# RocketWatch-TOP.net
KiCad netlist of a schematic drawn in EAGLE
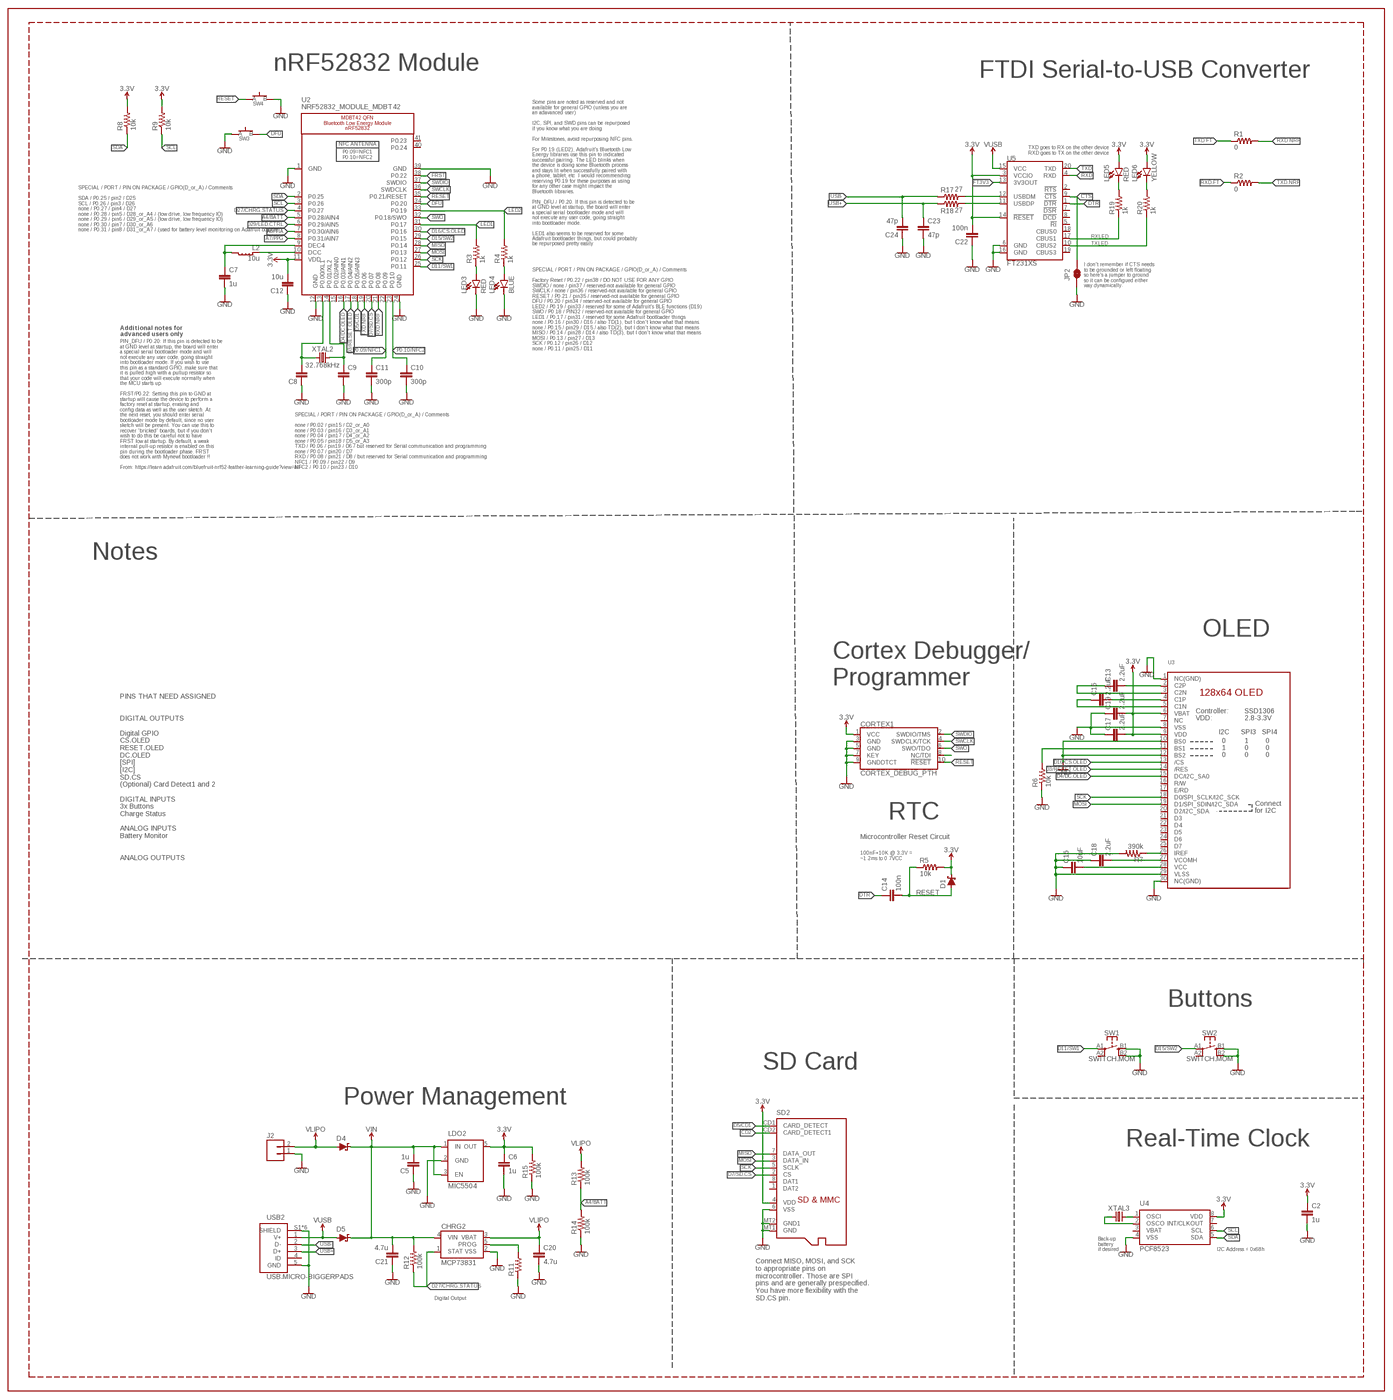
[diagram p0: schematic, sheet 1, overview]
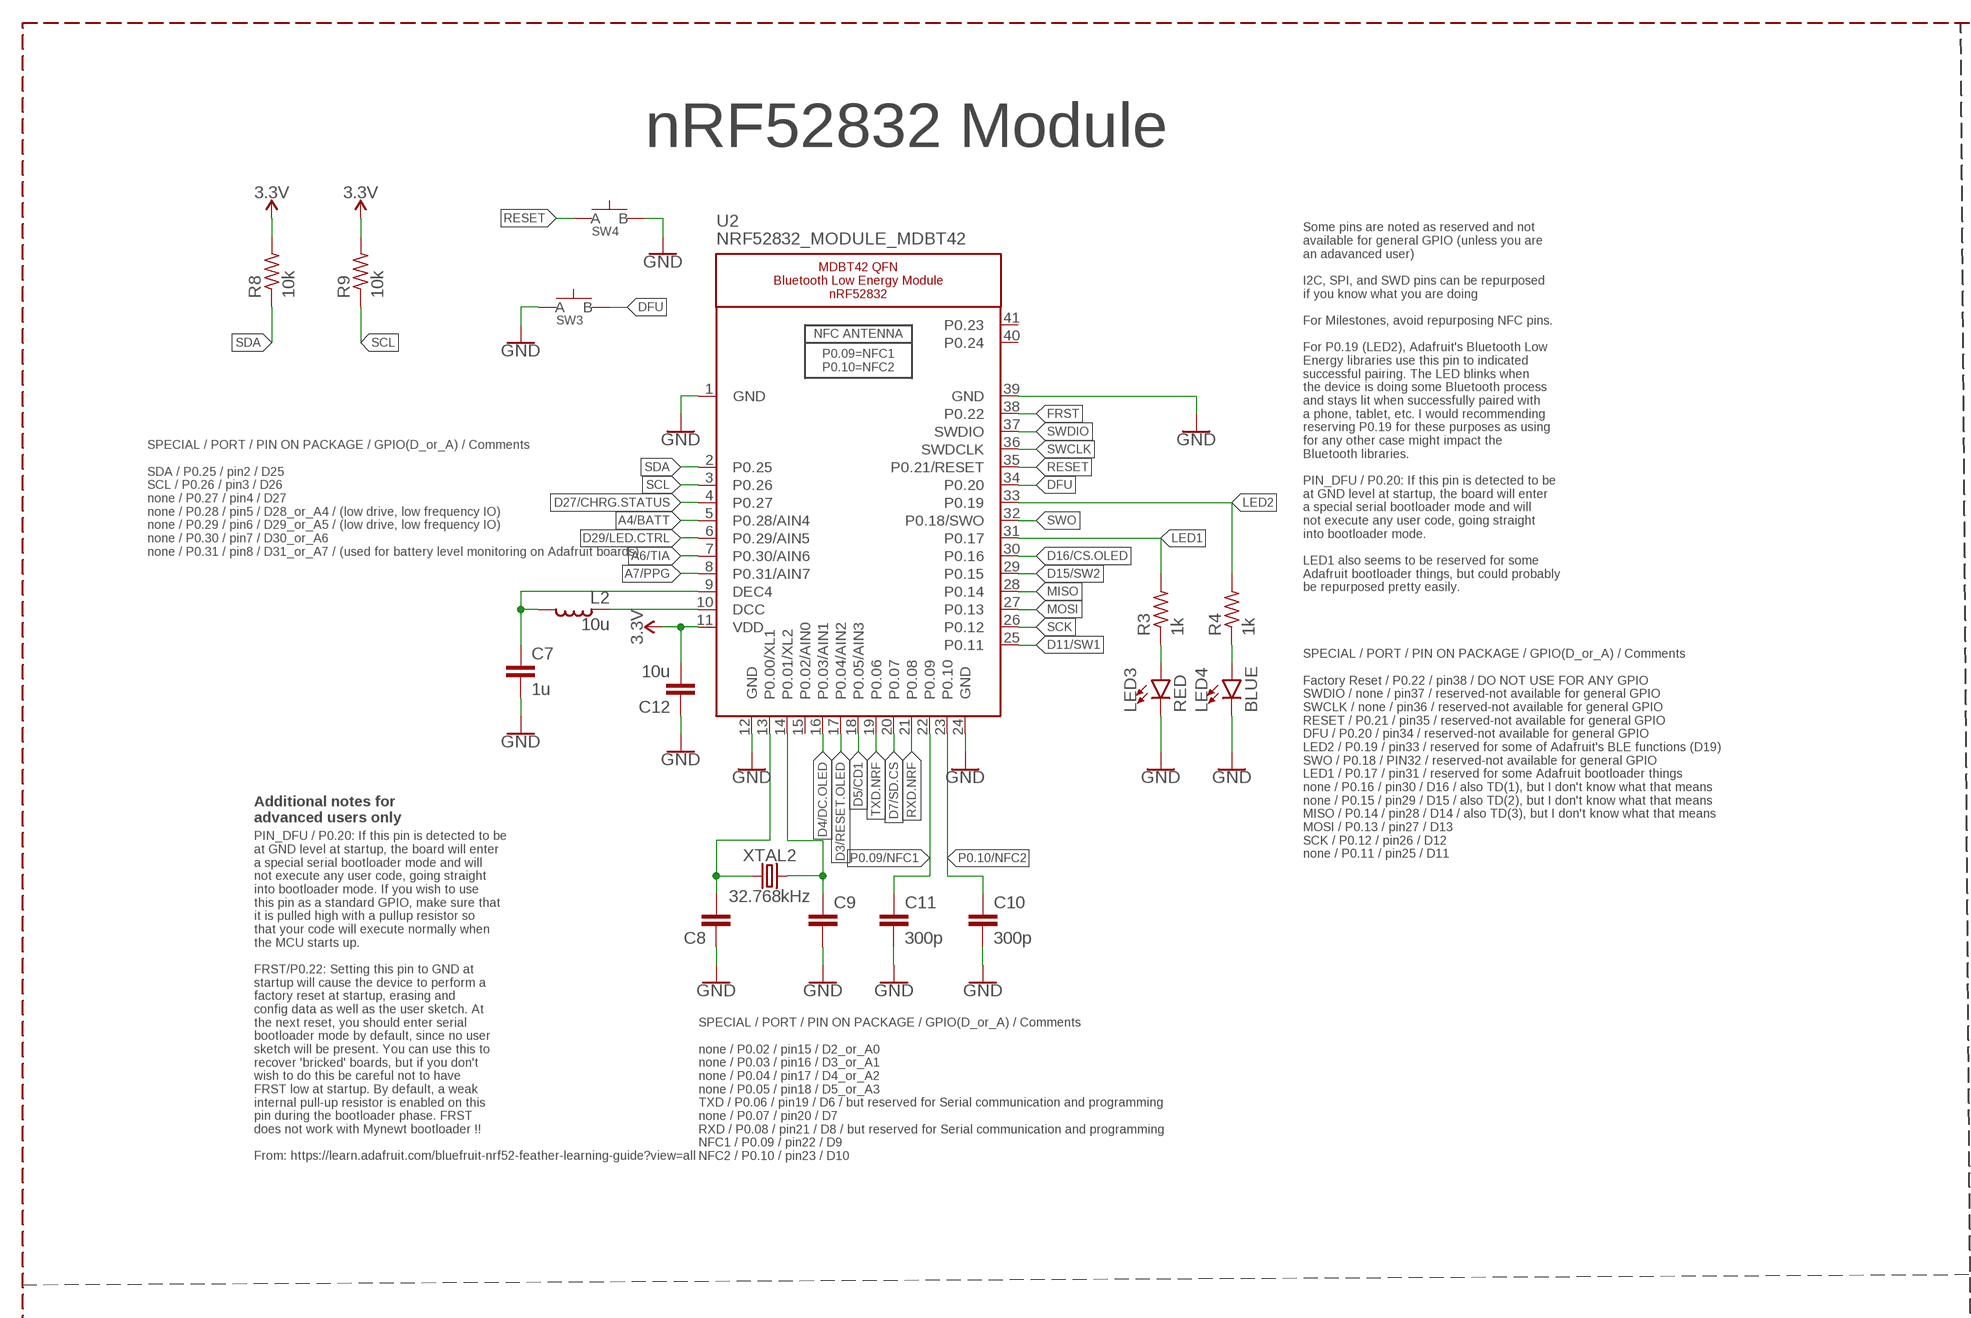
[diagram p1: schematic, sheet 1, part 1 of 4]
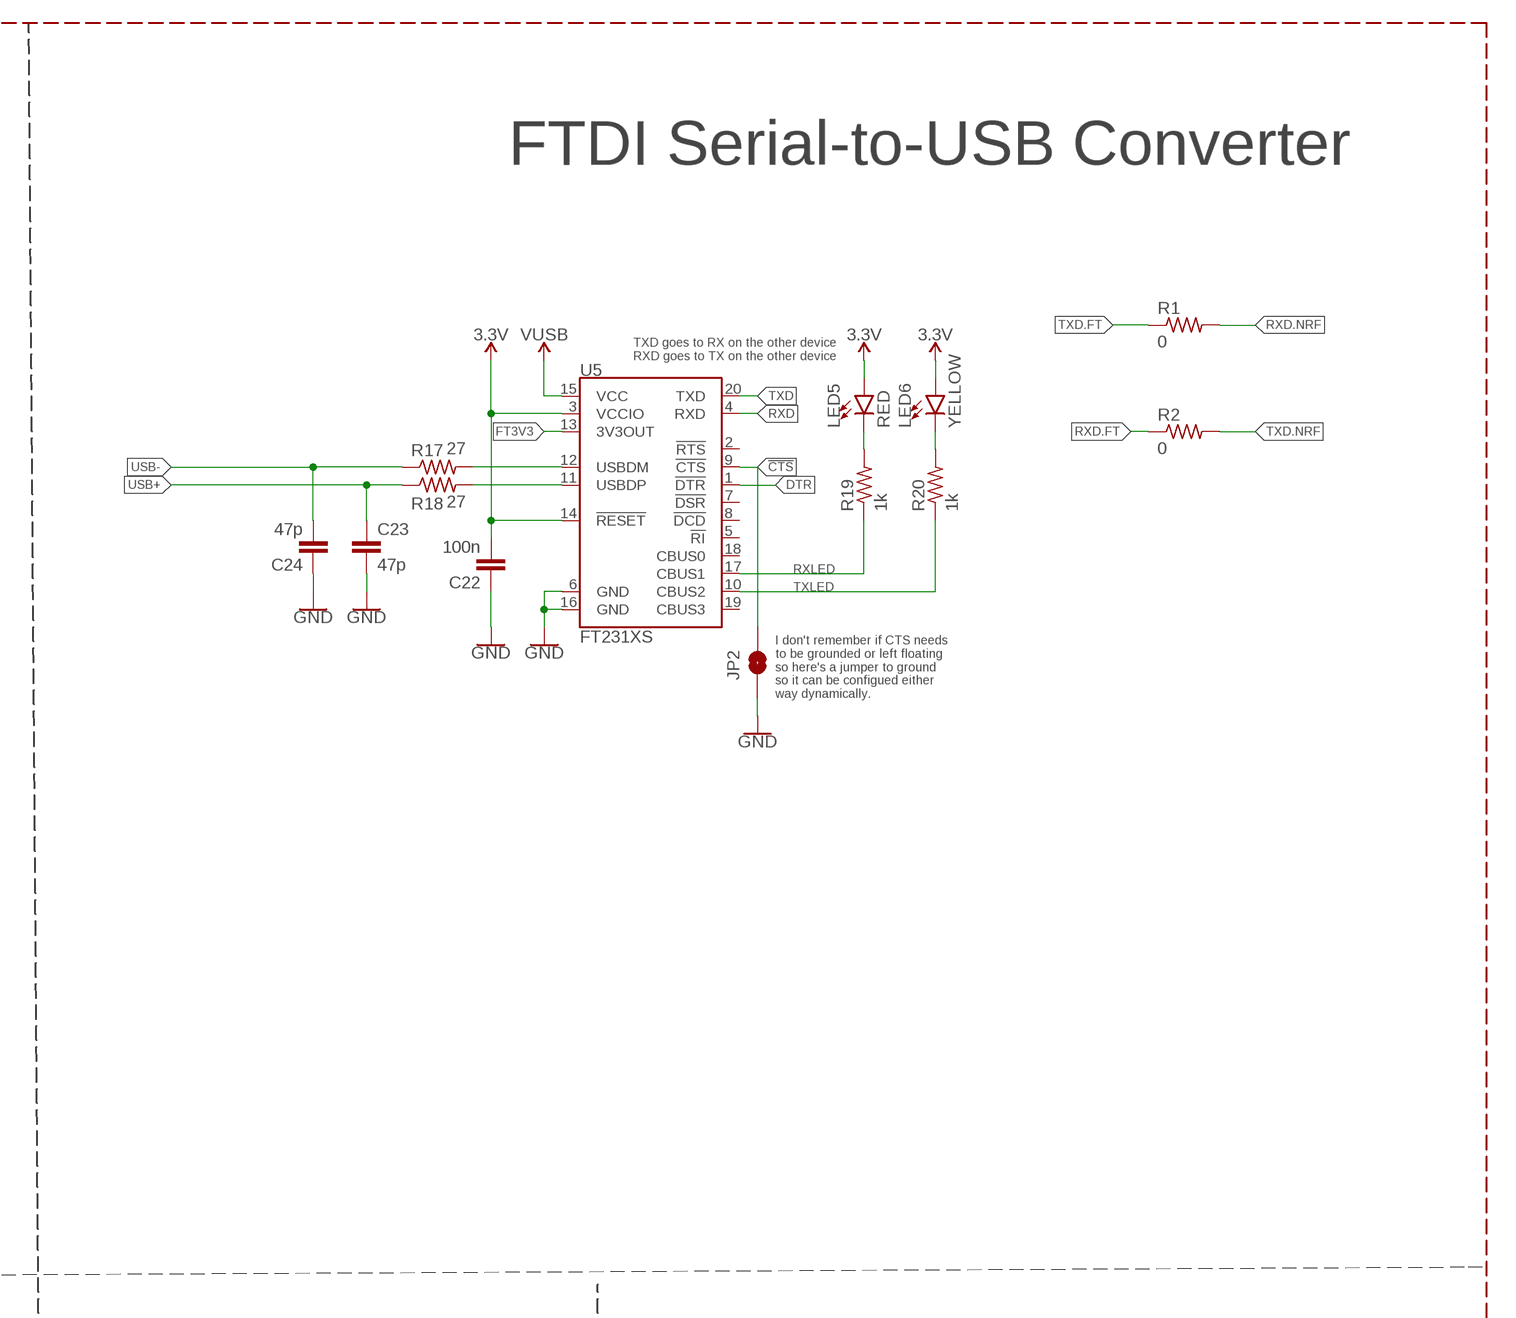
[diagram p2: schematic, sheet 1, part 2 of 4]
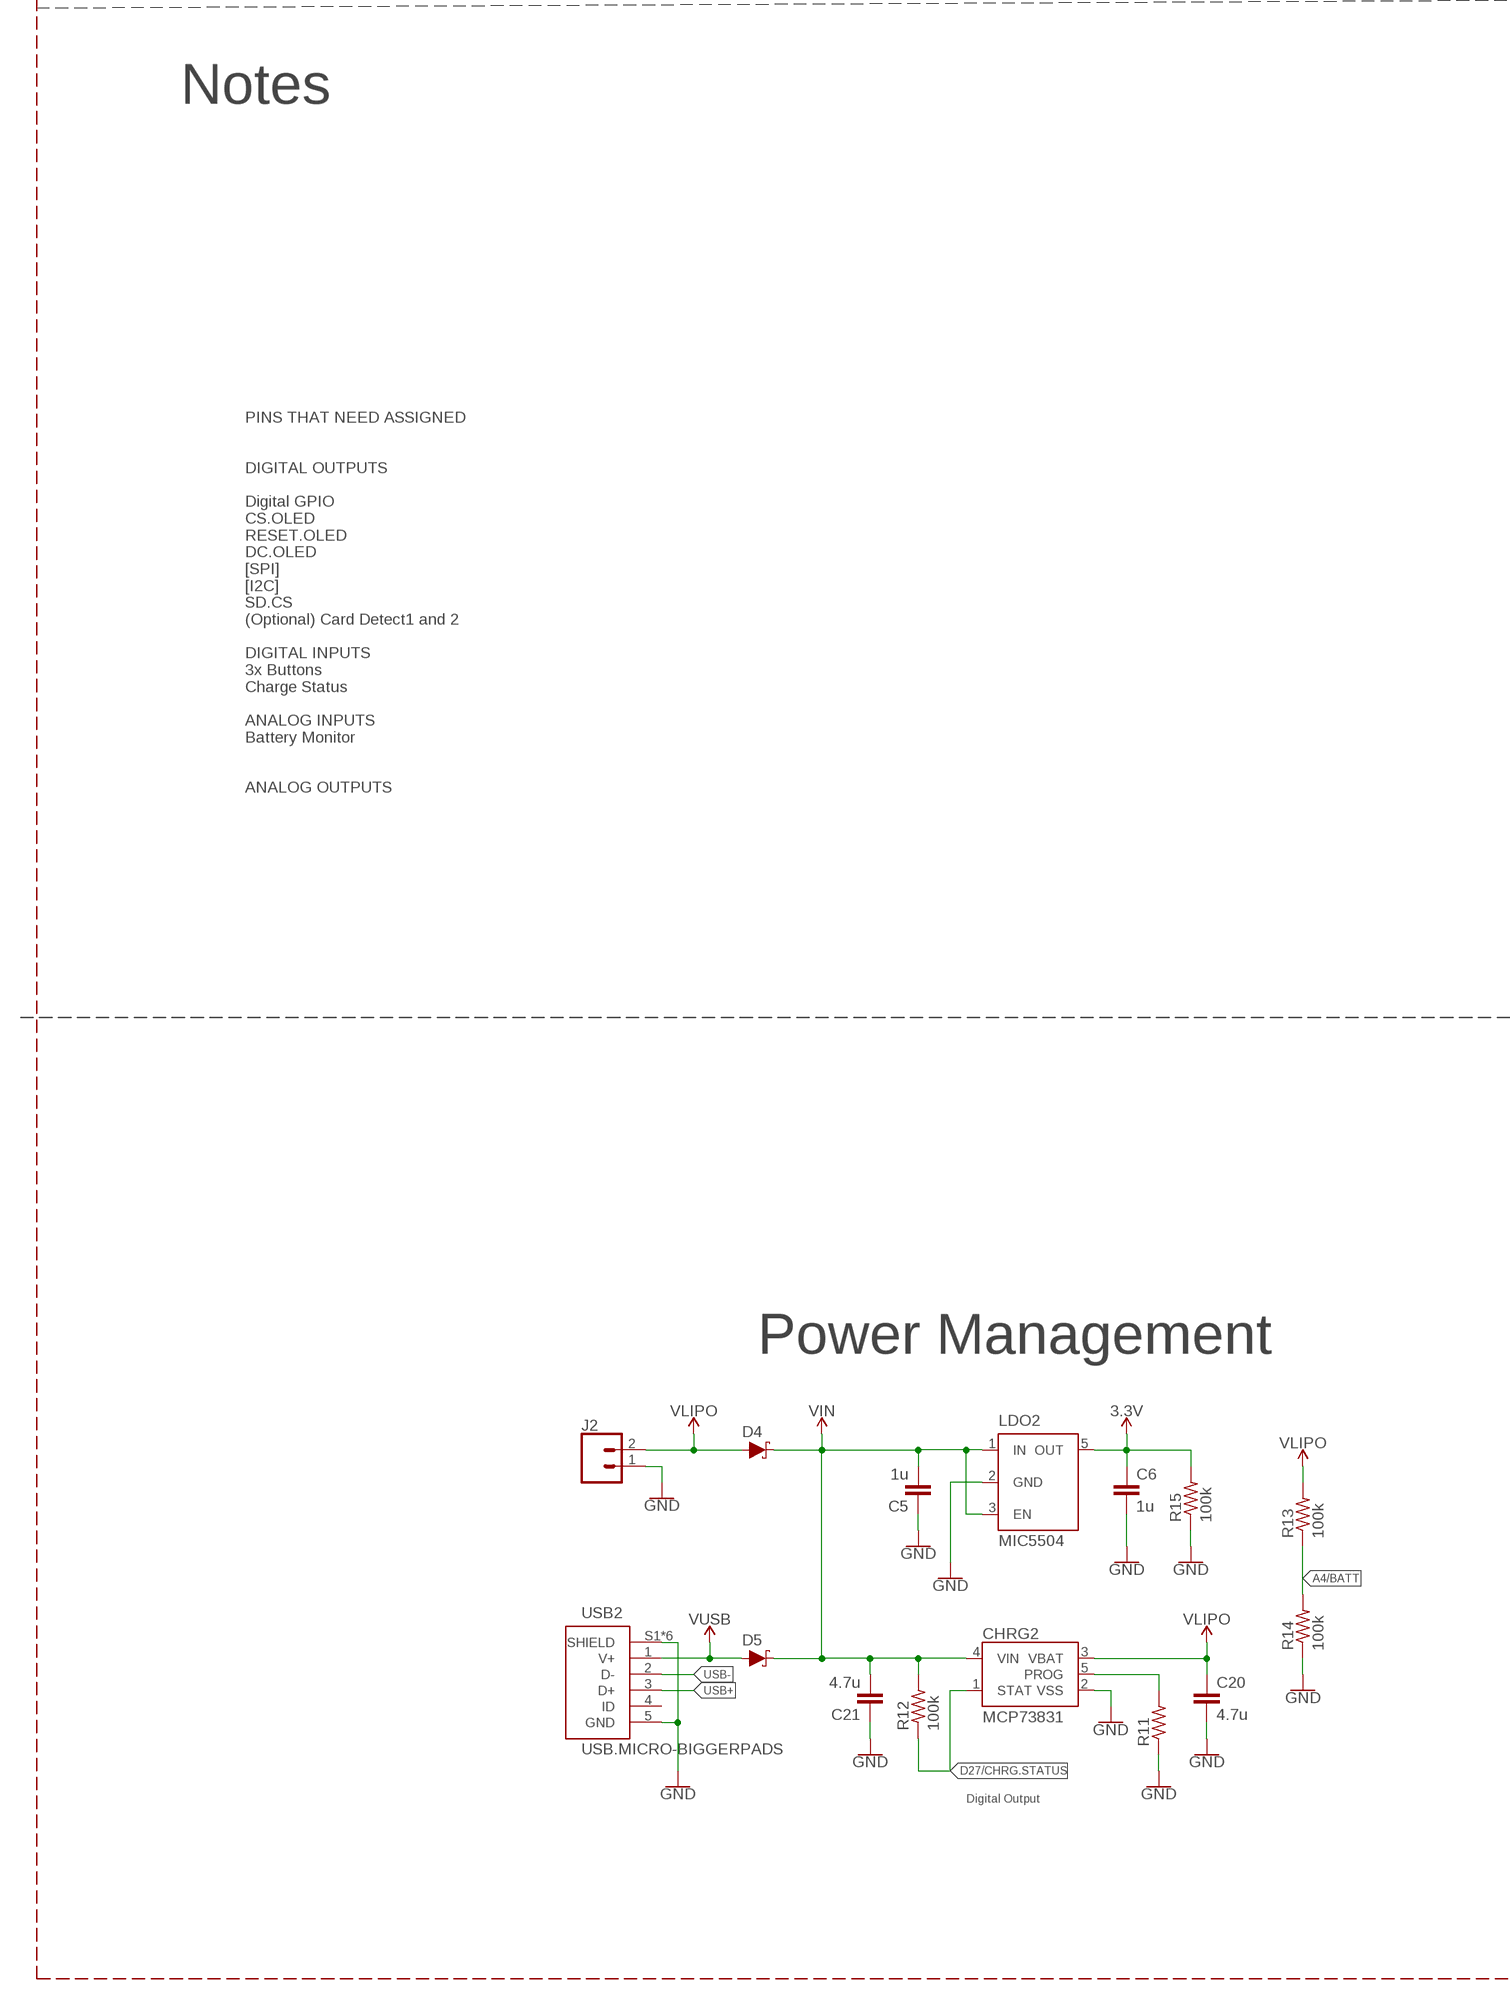
[diagram p3: schematic, sheet 1, part 3 of 4]
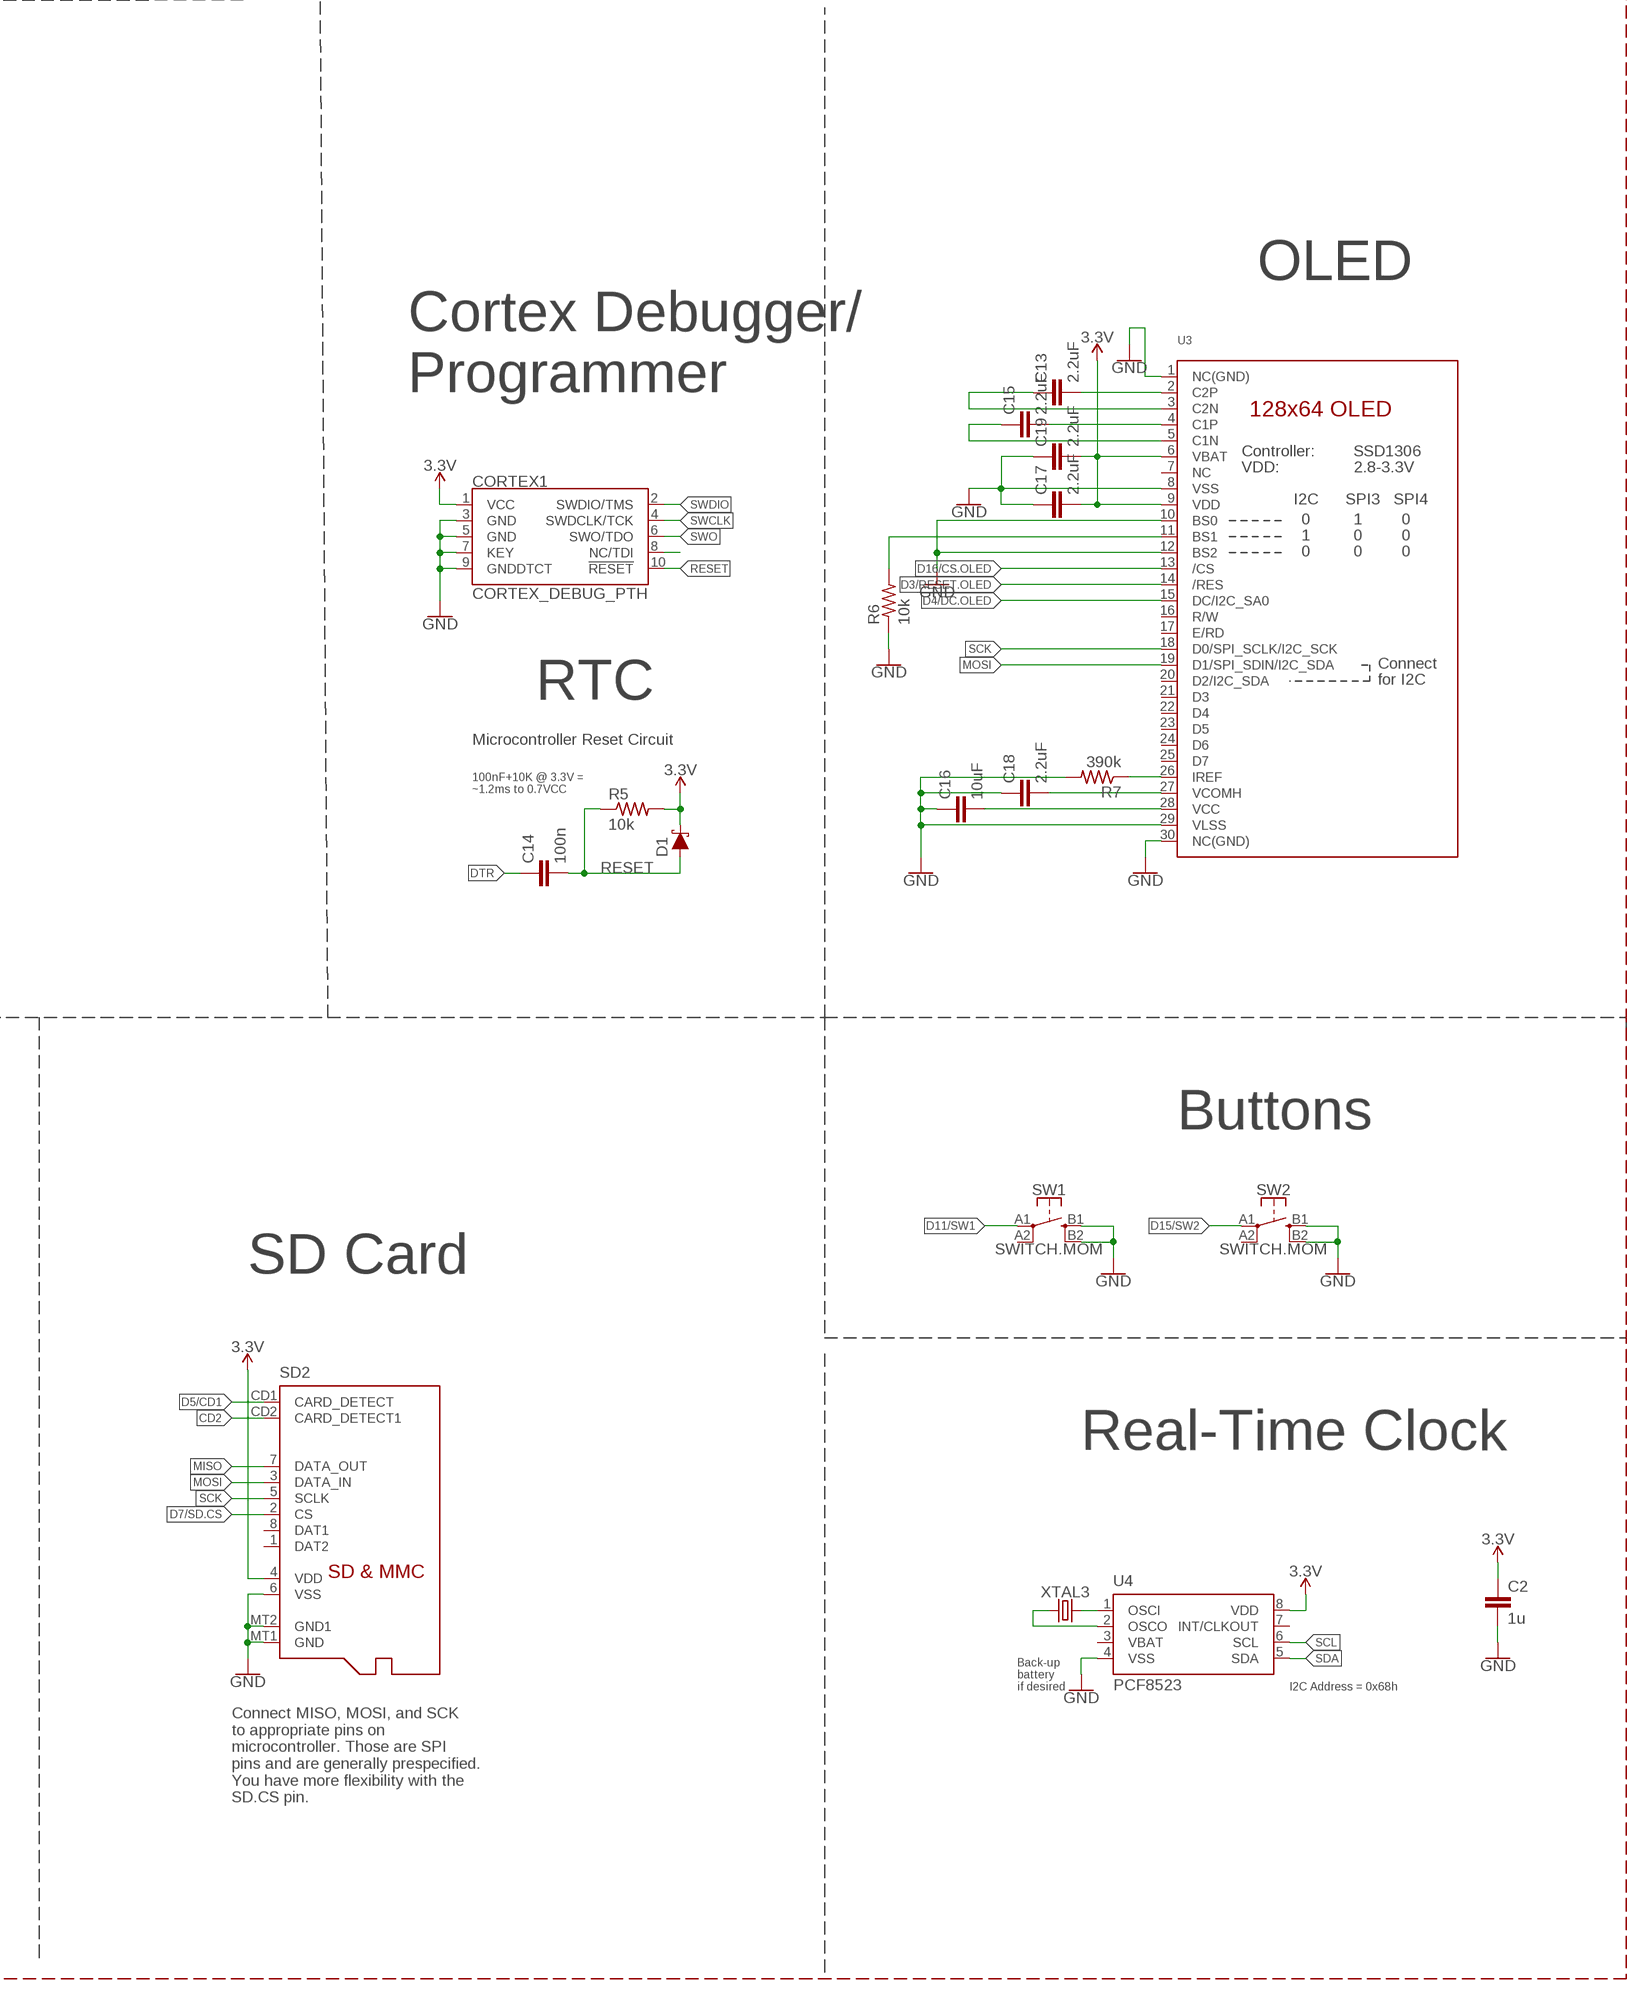
[diagram p4: schematic, sheet 1, part 4 of 4]

(export (version "E")
  (design (tool "Eeschema 10.0.6"))
  (components
    (comp (ref "C2")
      (value "1u")
      (footprint "eagle-import:C0603")
      (libsource (lib "eagle-import") (part "CAPACITOR0603"))
    )
    (comp (ref "C5")
      (value "1u")
      (footprint "eagle-import:C0603")
      (libsource (lib "eagle-import") (part "CAPACITOR0603"))
    )
    (comp (ref "C6")
      (value "1u")
      (footprint "eagle-import:C0603")
      (libsource (lib "eagle-import") (part "CAPACITOR0603"))
    )
    (comp (ref "C7")
      (value "1u")
      (footprint "eagle-import:C0603")
      (libsource (lib "eagle-import") (part "CAPACITOR0603"))
    )
    (comp (ref "C8")
      (value "CAPACITOR0603")
      (footprint "eagle-import:C0603")
      (libsource (lib "eagle-import") (part "CAPACITOR0603"))
    )
    (comp (ref "C9")
      (value "CAPACITOR0603")
      (footprint "eagle-import:C0603")
      (libsource (lib "eagle-import") (part "CAPACITOR0603"))
    )
    (comp (ref "C10")
      (value "300p")
      (footprint "eagle-import:C0603")
      (libsource (lib "eagle-import") (part "CAPACITOR0603"))
    )
    (comp (ref "C11")
      (value "300p")
      (footprint "eagle-import:C0603")
      (libsource (lib "eagle-import") (part "CAPACITOR0603"))
    )
    (comp (ref "C12")
      (value "10u")
      (footprint "eagle-import:C0805")
      (libsource (lib "eagle-import") (part "CAPACITOR0805"))
    )
    (comp (ref "C13")
      (value "2.2uF")
      (footprint "eagle-import:C0402")
      (libsource (lib "eagle-import") (part "CAPACITOR0402"))
    )
    (comp (ref "C14")
      (value "100n")
      (footprint "eagle-import:C0603")
      (libsource (lib "eagle-import") (part "CAPACITOR0603"))
    )
    (comp (ref "C15")
      (value "2.2uF")
      (footprint "eagle-import:C0402")
      (libsource (lib "eagle-import") (part "CAPACITOR0402"))
    )
    (comp (ref "C16")
      (value "10uF")
      (footprint "eagle-import:C0603")
      (libsource (lib "eagle-import") (part "CAPACITOR0603"))
    )
    (comp (ref "C17")
      (value "2.2uF")
      (footprint "eagle-import:C0402")
      (libsource (lib "eagle-import") (part "CAPACITOR0402"))
    )
    (comp (ref "C18")
      (value "2.2uF")
      (footprint "eagle-import:C0402")
      (libsource (lib "eagle-import") (part "CAPACITOR0402"))
    )
    (comp (ref "C19")
      (value "2.2uF")
      (footprint "eagle-import:C0402")
      (libsource (lib "eagle-import") (part "CAPACITOR0402"))
    )
    (comp (ref "C20")
      (value "4.7u")
      (footprint "eagle-import:C0603")
      (libsource (lib "eagle-import") (part "CAPACITOR0603"))
    )
    (comp (ref "C21")
      (value "4.7u")
      (footprint "eagle-import:C0603")
      (libsource (lib "eagle-import") (part "CAPACITOR0603"))
    )
    (comp (ref "C22")
      (value "100n")
      (footprint "eagle-import:C0603")
      (libsource (lib "eagle-import") (part "CAPACITOR0603"))
    )
    (comp (ref "C23")
      (value "47p")
      (footprint "eagle-import:C0603")
      (libsource (lib "eagle-import") (part "CAPACITOR0603"))
    )
    (comp (ref "C24")
      (value "47p")
      (footprint "eagle-import:C0603")
      (libsource (lib "eagle-import") (part "CAPACITOR0603"))
    )
    (comp (ref "CHRG2")
      (value "MCP73831")
      (footprint "eagle-import:SOT23-5")
      (libsource (lib "eagle-import") (part "MCP73831"))
    )
    (comp (ref "CORTEX1")
      (value "CORTEX_DEBUG_PTH")
      (footprint "eagle-import:2X5-PTH-1.27MM")
      (libsource (lib "eagle-import") (part "CORTEX_DEBUG_PTH"))
    )
    (comp (ref "D1")
      (value "SCHOTTKY-USC")
      (footprint "eagle-import:USC")
      (libsource (lib "eagle-import") (part "SCHOTTKY-USC"))
    )
    (comp (ref "D4")
      (value "SCHOTTKY-USC")
      (footprint "eagle-import:USC")
      (libsource (lib "eagle-import") (part "SCHOTTKY-USC"))
    )
    (comp (ref "D5")
      (value "SCHOTTKY-USC")
      (footprint "eagle-import:USC")
      (libsource (lib "eagle-import") (part "SCHOTTKY-USC"))
    )
    (comp (ref "J2")
      (value "CONN_02")
      (footprint "eagle-import:1X02")
      (libsource (lib "eagle-import") (part "CONN_02"))
    )
    (comp (ref "JP2")
      (value "JUMPER-SMT_2_NO_SILK")
      (footprint "eagle-import:SMT-JUMPER_2_NO_SILK")
      (libsource (lib "eagle-import") (part "JUMPER-SMT_2_NO_SILK"))
    )
    (comp (ref "L2")
      (value "10u")
      (footprint "eagle-import:L0603")
      (libsource (lib "eagle-import") (part "INDUCTOR0603"))
    )
    (comp (ref "LDO2")
      (value "MIC5504")
      (footprint "eagle-import:SOT23-5")
      (libsource (lib "eagle-import") (part "MIC5504"))
    )
    (comp (ref "LED3")
      (value "RED")
      (footprint "eagle-import:LED-0603")
      (libsource (lib "eagle-import") (part "LED0603"))
    )
    (comp (ref "LED4")
      (value "BLUE")
      (footprint "eagle-import:LED-0603")
      (libsource (lib "eagle-import") (part "LED0603"))
    )
    (comp (ref "LED5")
      (value "RED")
      (footprint "eagle-import:LED-0603")
      (libsource (lib "eagle-import") (part "LED0603"))
    )
    (comp (ref "LED6")
      (value "YELLOW")
      (footprint "eagle-import:LED-0603")
      (libsource (lib "eagle-import") (part "LED0603"))
    )
    (comp (ref "R1")
      (value "0")
      (footprint "eagle-import:R0603")
      (libsource (lib "eagle-import") (part "RESISTOR0603"))
    )
    (comp (ref "R2")
      (value "0")
      (footprint "eagle-import:R0603")
      (libsource (lib "eagle-import") (part "RESISTOR0603"))
    )
    (comp (ref "R3")
      (value "1k")
      (footprint "eagle-import:R0603")
      (libsource (lib "eagle-import") (part "RESISTOR0603"))
    )
    (comp (ref "R4")
      (value "1k")
      (footprint "eagle-import:R0603")
      (libsource (lib "eagle-import") (part "RESISTOR0603"))
    )
    (comp (ref "R5")
      (value "10k")
      (footprint "eagle-import:R0603")
      (libsource (lib "eagle-import") (part "RESISTOR0603"))
    )
    (comp (ref "R6")
      (value "10k")
      (footprint "eagle-import:R0603")
      (libsource (lib "eagle-import") (part "RESISTOR0603"))
    )
    (comp (ref "R7")
      (value "390k")
      (footprint "eagle-import:R0603")
      (libsource (lib "eagle-import") (part "RESISTOR0603"))
    )
    (comp (ref "R8")
      (value "10k")
      (footprint "eagle-import:R0603")
      (libsource (lib "eagle-import") (part "RESISTOR0603"))
    )
    (comp (ref "R9")
      (value "10k")
      (footprint "eagle-import:R0603")
      (libsource (lib "eagle-import") (part "RESISTOR0603"))
    )
    (comp (ref "R11")
      (value "RESISTOR0603")
      (footprint "eagle-import:R0603")
      (libsource (lib "eagle-import") (part "RESISTOR0603"))
    )
    (comp (ref "R12")
      (value "100k")
      (footprint "eagle-import:R0603")
      (libsource (lib "eagle-import") (part "RESISTOR0603"))
    )
    (comp (ref "R13")
      (value "100k")
      (footprint "eagle-import:R0603")
      (libsource (lib "eagle-import") (part "RESISTOR0603"))
    )
    (comp (ref "R14")
      (value "100k")
      (footprint "eagle-import:R0603")
      (libsource (lib "eagle-import") (part "RESISTOR0603"))
    )
    (comp (ref "R15")
      (value "100k")
      (footprint "eagle-import:R0603")
      (libsource (lib "eagle-import") (part "RESISTOR0603"))
    )
    (comp (ref "R17")
      (value "27")
      (footprint "eagle-import:R0603")
      (libsource (lib "eagle-import") (part "RESISTOR0603"))
    )
    (comp (ref "R18")
      (value "27")
      (footprint "eagle-import:R0603")
      (libsource (lib "eagle-import") (part "RESISTOR0603"))
    )
    (comp (ref "R19")
      (value "1k")
      (footprint "eagle-import:R0603")
      (libsource (lib "eagle-import") (part "RESISTOR0603"))
    )
    (comp (ref "R20")
      (value "1k")
      (footprint "eagle-import:R0603")
      (libsource (lib "eagle-import") (part "RESISTOR0603"))
    )
    (comp (ref "SD2")
      (value "MICROSD")
      (footprint "eagle-import:MICROSD")
      (libsource (lib "eagle-import") (part "MICROSD"))
    )
    (comp (ref "SW1")
      (value "SWITCH.MOM")
      (footprint "eagle-import:TACTILE_SWITCH_SMD_6.2MM_TALL")
      (libsource (lib "eagle-import") (part "SWITCH.MOM"))
    )
    (comp (ref "SW2")
      (value "SWITCH.MOM")
      (footprint "eagle-import:TACTILE_SWITCH_SMD_6.2MM_TALL")
      (libsource (lib "eagle-import") (part "SWITCH.MOM"))
    )
    (comp (ref "SW3")
      (value "SPST-PTS830GG140-COPY.1-3")
      (footprint "eagle-import:BUTTON-GULLWING")
      (libsource (lib "eagle-import") (part "SPST-PTS830GG140-COPY.1-3"))
    )
    (comp (ref "SW4")
      (value "SPST-PTS830GG140-COPY.1-3")
      (footprint "eagle-import:BUTTON-GULLWING")
      (libsource (lib "eagle-import") (part "SPST-PTS830GG140-COPY.1-3"))
    )
    (comp (ref "U2")
      (value "NRF52832_MODULE_MDBT42")
      (footprint "eagle-import:BLE_MODULE_RAYTAC_MDBT42")
      (libsource (lib "eagle-import") (part "NRF52832_MODULE_MDBT42"))
    )
    (comp (ref "U3")
      (value "DISP_OLED_UG-2864HSWEG01-NO-WRAPAROUND")
      (footprint "eagle-import:UG-2864HSWEG01_0.96IN_NO-WRAPAROUND")
      (libsource (lib "eagle-import") (part "DISP_OLED_UG-2864HSWEG01-NO-WRAPAROUND"))
    )
    (comp (ref "U4")
      (value "PCF8523")
      (footprint "eagle-import:SO8")
      (libsource (lib "eagle-import") (part "PCF8523"))
    )
    (comp (ref "U5")
      (value "FT231XS")
      (footprint "eagle-import:SSOP20_L")
      (libsource (lib "eagle-import") (part "FT231XS"))
    )
    (comp (ref "USB2")
      (value "USB.MICRO-BIGGERPADS")
      (footprint "eagle-import:USB-MICRO-01.BIGGERPADS")
      (libsource (lib "eagle-import") (part "USB.MICRO-BIGGERPADS"))
    )
    (comp (ref "XTAL2")
      (value "32.768kHz")
      (footprint "eagle-import:2-SMD.NOLEAD.2.0MMTO1.2MM")
      (libsource (lib "eagle-import") (part "CRYSTALECS-.327-12.5-12-C-TR"))
    )
    (comp (ref "XTAL3")
      (value "32.7680kHz")
      (footprint "eagle-import:2-SMD.NOLEAD.2.0MMTO1.2MM")
      (fields (field (name "FREQ") "32.7680KHZ"))
      (libsource (lib "eagle-import") (part "CRYSTALECS-.327-12.5-12-C-TR"))
    )
  )
  (nets
    (net (code "1") (name "/RXLED") (class "Default")
      (node (ref "R19") (pin "1") (pinfunction "1_1") (pintype "passive"))
      (node (ref "U5") (pin "17") (pinfunction "CBUS1_17") (pintype "bidirectional"))
    )
    (net (code "2") (name "/TXLED") (class "Default")
      (node (ref "R20") (pin "1") (pinfunction "1_1") (pintype "passive"))
      (node (ref "U5") (pin "10") (pinfunction "CBUS2_10") (pintype "bidirectional"))
    )
    (net (code "3") (name "/VBAT") (class "Default")
      (node (ref "U4") (pin "3") (pinfunction "VBAT_3") (pintype "power_in"))
    )
    (net (code "4") (name "/~{CTS}") (class "Default")
      (node (ref "JP2") (pin "2") (pinfunction "2_2") (pintype "passive"))
      (node (ref "U5") (pin "9") (pinfunction "~{CTS}_9") (pintype "bidirectional"))
    )
    (net (code "5") (name "3.3V") (class "Default")
      (node (ref "C12") (pin "2") (pinfunction "2_2") (pintype "passive"))
      (node (ref "C17") (pin "2") (pinfunction "2_2") (pintype "passive"))
      (node (ref "C19") (pin "2") (pinfunction "2_2") (pintype "passive"))
      (node (ref "C2") (pin "1") (pinfunction "1_1") (pintype "passive"))
      (node (ref "C22") (pin "2") (pinfunction "2_2") (pintype "passive"))
      (node (ref "C6") (pin "1") (pinfunction "1_1") (pintype "passive"))
      (node (ref "CORTEX1") (pin "1") (pinfunction "VCC_1") (pintype "bidirectional"))
      (node (ref "D1") (pin "-") (pinfunction "C_-") (pintype "passive"))
      (node (ref "LDO2") (pin "5") (pinfunction "OUT_5") (pintype "bidirectional"))
      (node (ref "LED5") (pin "A") (pinfunction "A_A") (pintype "passive"))
      (node (ref "LED6") (pin "A") (pinfunction "A_A") (pintype "passive"))
      (node (ref "R15") (pin "2") (pinfunction "2_2") (pintype "passive"))
      (node (ref "R5") (pin "2") (pinfunction "2_2") (pintype "passive"))
      (node (ref "R8") (pin "2") (pinfunction "2_2") (pintype "passive"))
      (node (ref "R9") (pin "2") (pinfunction "2_2") (pintype "passive"))
      (node (ref "SD2") (pin "4") (pinfunction "VDD_4") (pintype "power_in"))
      (node (ref "U2") (pin "11") (pinfunction "VDD_11") (pintype "bidirectional"))
      (node (ref "U3") (pin "6") (pinfunction "VBAT_6") (pintype "input"))
      (node (ref "U3") (pin "9") (pinfunction "VDD_9") (pintype "power_in"))
      (node (ref "U4") (pin "8") (pinfunction "VDD_8") (pintype "power_in"))
      (node (ref "U5") (pin "14") (pinfunction "~{RESET}_14") (pintype "bidirectional"))
      (node (ref "U5") (pin "3") (pinfunction "VCCIO_3") (pintype "bidirectional"))
    )
    (net (code "6") (name "A4{slash}BATT") (class "Default")
      (node (ref "R13") (pin "1") (pinfunction "1_1") (pintype "passive"))
      (node (ref "R14") (pin "2") (pinfunction "2_2") (pintype "passive"))
      (node (ref "U2") (pin "5") (pinfunction "P0.28/AIN4_5") (pintype "bidirectional"))
    )
    (net (code "7") (name "A6{slash}TIA") (class "Default")
      (node (ref "U2") (pin "7") (pinfunction "P0.30/AIN6_7") (pintype "bidirectional"))
    )
    (net (code "8") (name "A7{slash}PPG") (class "Default")
      (node (ref "U2") (pin "8") (pinfunction "P0.31/AIN7_8") (pintype "bidirectional"))
    )
    (net (code "9") (name "CD2") (class "Default")
      (node (ref "SD2") (pin "CD2") (pinfunction "CARD_DETECT1_CD2") (pintype "passive"))
    )
    (net (code "10") (name "D3{slash}RESET.OLED") (class "Default")
      (node (ref "U2") (pin "17") (pinfunction "P0.04/AIN2_17") (pintype "bidirectional"))
      (node (ref "U3") (pin "14") (pinfunction "/RES_14") (pintype "input"))
    )
    (net (code "11") (name "D4{slash}DC.OLED") (class "Default")
      (node (ref "U2") (pin "16") (pinfunction "P0.03/AIN1_16") (pintype "bidirectional"))
      (node (ref "U3") (pin "15") (pinfunction "DC/I2C_SA0_15") (pintype "input"))
    )
    (net (code "12") (name "D5{slash}CD1") (class "Default")
      (node (ref "SD2") (pin "CD1") (pinfunction "CARD_DETECT_CD1") (pintype "passive"))
      (node (ref "U2") (pin "18") (pinfunction "P0.05/AIN3_18") (pintype "bidirectional"))
    )
    (net (code "13") (name "D7{slash}SD.CS") (class "Default")
      (node (ref "SD2") (pin "2") (pinfunction "CS_2") (pintype "input"))
      (node (ref "U2") (pin "20") (pinfunction "P0.07_20") (pintype "bidirectional"))
    )
    (net (code "14") (name "D11{slash}SW1") (class "Default")
      (node (ref "SW1") (pin "A1") (pinfunction "1_A1") (pintype "passive"))
      (node (ref "U2") (pin "25") (pinfunction "P0.11_25") (pintype "bidirectional"))
    )
    (net (code "15") (name "D15{slash}SW2") (class "Default")
      (node (ref "SW2") (pin "A1") (pinfunction "1_A1") (pintype "passive"))
      (node (ref "U2") (pin "29") (pinfunction "P0.15_29") (pintype "bidirectional"))
    )
    (net (code "16") (name "D16{slash}CS.OLED") (class "Default")
      (node (ref "U2") (pin "30") (pinfunction "P0.16_30") (pintype "bidirectional"))
      (node (ref "U3") (pin "13") (pinfunction "/CS_13") (pintype "input"))
    )
    (net (code "17") (name "D27{slash}CHRG.STATUS") (class "Default")
      (node (ref "CHRG2") (pin "1") (pinfunction "STAT_1") (pintype "output"))
      (node (ref "R12") (pin "1") (pinfunction "1_1") (pintype "passive"))
      (node (ref "U2") (pin "4") (pinfunction "P0.27_4") (pintype "bidirectional"))
    )
    (net (code "18") (name "D29{slash}LED.CTRL") (class "Default")
      (node (ref "U2") (pin "6") (pinfunction "P0.29/AIN5_6") (pintype "bidirectional"))
    )
    (net (code "19") (name "DFU") (class "Default")
      (node (ref "SW3") (pin "3") (pinfunction "B_3") (pintype "bidirectional"))
      (node (ref "U2") (pin "34") (pinfunction "P0.20_34") (pintype "bidirectional"))
    )
    (net (code "20") (name "DTR") (class "Default")
      (node (ref "C14") (pin "1") (pinfunction "1_1") (pintype "passive"))
      (node (ref "U5") (pin "1") (pinfunction "~{DTR}_1") (pintype "bidirectional"))
    )
    (net (code "21") (name "FRST") (class "Default")
      (node (ref "U2") (pin "38") (pinfunction "P0.22_38") (pintype "bidirectional"))
    )
    (net (code "22") (name "FT3V3") (class "Default")
      (node (ref "U5") (pin "13") (pinfunction "3V3OUT_13") (pintype "bidirectional"))
    )
    (net (code "23") (name "GND") (class "Default")
      (node (ref "C10") (pin "2") (pinfunction "2_2") (pintype "passive"))
      (node (ref "C11") (pin "2") (pinfunction "2_2") (pintype "passive"))
      (node (ref "C12") (pin "1") (pinfunction "1_1") (pintype "passive"))
      (node (ref "C16") (pin "1") (pinfunction "1_1") (pintype "passive"))
      (node (ref "C17") (pin "1") (pinfunction "1_1") (pintype "passive"))
      (node (ref "C18") (pin "1") (pinfunction "1_1") (pintype "passive"))
      (node (ref "C19") (pin "1") (pinfunction "1_1") (pintype "passive"))
      (node (ref "C2") (pin "2") (pinfunction "2_2") (pintype "passive"))
      (node (ref "C20") (pin "2") (pinfunction "2_2") (pintype "passive"))
      (node (ref "C21") (pin "1") (pinfunction "1_1") (pintype "passive"))
      (node (ref "C22") (pin "1") (pinfunction "1_1") (pintype "passive"))
      (node (ref "C23") (pin "2") (pinfunction "2_2") (pintype "passive"))
      (node (ref "C24") (pin "1") (pinfunction "1_1") (pintype "passive"))
      (node (ref "C5") (pin "1") (pinfunction "1_1") (pintype "passive"))
      (node (ref "C6") (pin "2") (pinfunction "2_2") (pintype "passive"))
      (node (ref "C7") (pin "2") (pinfunction "2_2") (pintype "passive"))
      (node (ref "C8") (pin "1") (pinfunction "1_1") (pintype "passive"))
      (node (ref "C9") (pin "2") (pinfunction "2_2") (pintype "passive"))
      (node (ref "CHRG2") (pin "2") (pinfunction "VSS_2") (pintype "power_in"))
      (node (ref "CORTEX1") (pin "3") (pinfunction "GND_3") (pintype "bidirectional"))
      (node (ref "CORTEX1") (pin "5") (pinfunction "GND_5") (pintype "bidirectional"))
      (node (ref "CORTEX1") (pin "7") (pinfunction "KEY_7") (pintype "bidirectional"))
      (node (ref "CORTEX1") (pin "9") (pinfunction "GNDDTCT_9") (pintype "bidirectional"))
      (node (ref "J2") (pin "1") (pinfunction "1_1") (pintype "passive"))
      (node (ref "JP2") (pin "1") (pinfunction "1_1") (pintype "passive"))
      (node (ref "LDO2") (pin "2") (pinfunction "GND_2") (pintype "bidirectional"))
      (node (ref "LED3") (pin "C") (pinfunction "C_C") (pintype "passive"))
      (node (ref "LED4") (pin "C") (pinfunction "C_C") (pintype "passive"))
      (node (ref "R11") (pin "1") (pinfunction "1_1") (pintype "passive"))
      (node (ref "R14") (pin "1") (pinfunction "1_1") (pintype "passive"))
      (node (ref "R15") (pin "1") (pinfunction "1_1") (pintype "passive"))
      (node (ref "R6") (pin "1") (pinfunction "1_1") (pintype "passive"))
      (node (ref "R7") (pin "2") (pinfunction "2_2") (pintype "passive"))
      (node (ref "SD2") (pin "6") (pinfunction "VSS_6") (pintype "power_in"))
      (node (ref "SD2") (pin "MT1") (pinfunction "GND_MT1") (pintype "power_in"))
      (node (ref "SD2") (pin "MT2") (pinfunction "GND1_MT2") (pintype "power_in"))
      (node (ref "SW1") (pin "B1") (pinfunction "3_B1") (pintype "passive"))
      (node (ref "SW1") (pin "B2") (pinfunction "4_B2") (pintype "passive"))
      (node (ref "SW2") (pin "B1") (pinfunction "3_B1") (pintype "passive"))
      (node (ref "SW2") (pin "B2") (pinfunction "4_B2") (pintype "passive"))
      (node (ref "SW3") (pin "1") (pinfunction "A_1") (pintype "bidirectional"))
      (node (ref "SW4") (pin "3") (pinfunction "B_3") (pintype "bidirectional"))
      (node (ref "U2") (pin "1") (pinfunction "GND_1") (pintype "bidirectional"))
      (node (ref "U2") (pin "12") (pinfunction "GND_12") (pintype "bidirectional"))
      (node (ref "U2") (pin "24") (pinfunction "GND_24") (pintype "bidirectional"))
      (node (ref "U2") (pin "39") (pinfunction "GND_39") (pintype "bidirectional"))
      (node (ref "U3") (pin "1") (pinfunction "NC(GND)_1") (pintype "input"))
      (node (ref "U3") (pin "10") (pinfunction "BS0_10") (pintype "input"))
      (node (ref "U3") (pin "12") (pinfunction "BS2_12") (pintype "input"))
      (node (ref "U3") (pin "29") (pinfunction "VLSS_29") (pintype "power_in"))
      (node (ref "U3") (pin "30") (pinfunction "NC(GND)_30") (pintype "input"))
      (node (ref "U3") (pin "8") (pinfunction "VSS_8") (pintype "power_in"))
      (node (ref "U4") (pin "4") (pinfunction "VSS_4") (pintype "power_in"))
      (node (ref "U5") (pin "16") (pinfunction "GND_16") (pintype "bidirectional"))
      (node (ref "U5") (pin "6") (pinfunction "GND_6") (pintype "bidirectional"))
      (node (ref "USB2") (pin "5") (pinfunction "GND_5") (pintype "bidirectional"))
      (node (ref "USB2") (pin "S1") (pinfunction "SHIELD_S1") (pintype "bidirectional"))
      (node (ref "USB2") (pin "S2") (pinfunction "SHIELD_S2") (pintype "bidirectional"))
      (node (ref "USB2") (pin "S3") (pinfunction "SHIELD_S3") (pintype "bidirectional"))
      (node (ref "USB2") (pin "S4") (pinfunction "SHIELD_S4") (pintype "bidirectional"))
      (node (ref "USB2") (pin "S5") (pinfunction "SHIELD_S5") (pintype "bidirectional"))
      (node (ref "USB2") (pin "S6") (pinfunction "SHIELD_S6") (pintype "bidirectional"))
    )
    (net (code "24") (name "LED1") (class "Default")
      (node (ref "R3") (pin "2") (pinfunction "2_2") (pintype "passive"))
      (node (ref "U2") (pin "31") (pinfunction "P0.17_31") (pintype "bidirectional"))
    )
    (net (code "25") (name "LED2") (class "Default")
      (node (ref "R4") (pin "2") (pinfunction "2_2") (pintype "passive"))
      (node (ref "U2") (pin "33") (pinfunction "P0.19_33") (pintype "bidirectional"))
    )
    (net (code "26") (name "MISO") (class "Default")
      (node (ref "SD2") (pin "7") (pinfunction "DATA_OUT_7") (pintype "output"))
      (node (ref "U2") (pin "28") (pinfunction "P0.14_28") (pintype "bidirectional"))
    )
    (net (code "27") (name "MOSI") (class "Default")
      (node (ref "SD2") (pin "3") (pinfunction "DATA_IN_3") (pintype "input"))
      (node (ref "U2") (pin "27") (pinfunction "P0.13_27") (pintype "bidirectional"))
      (node (ref "U3") (pin "19") (pinfunction "D1/SPI_SDIN/I2C_SDA_19") (pintype "bidirectional"))
    )
    (net (code "28") (name "Net-(CHRG2-PROG)") (class "Default")
      (node (ref "CHRG2") (pin "5") (pinfunction "PROG_5") (pintype "input"))
      (node (ref "R11") (pin "2") (pinfunction "2_2") (pintype "passive"))
    )
    (net (code "29") (name "Net-(LED3-PadA)") (class "Default")
      (node (ref "LED3") (pin "A") (pinfunction "A_A") (pintype "passive"))
      (node (ref "R3") (pin "1") (pinfunction "1_1") (pintype "passive"))
    )
    (net (code "30") (name "Net-(LED4-PadA)") (class "Default")
      (node (ref "LED4") (pin "A") (pinfunction "A_A") (pintype "passive"))
      (node (ref "R4") (pin "1") (pinfunction "1_1") (pintype "passive"))
    )
    (net (code "31") (name "Net-(LED5-PadC)") (class "Default")
      (node (ref "LED5") (pin "C") (pinfunction "C_C") (pintype "passive"))
      (node (ref "R19") (pin "2") (pinfunction "2_2") (pintype "passive"))
    )
    (net (code "32") (name "Net-(LED6-PadC)") (class "Default")
      (node (ref "LED6") (pin "C") (pinfunction "C_C") (pintype "passive"))
      (node (ref "R20") (pin "2") (pinfunction "2_2") (pintype "passive"))
    )
    (net (code "33") (name "Net-(U2-DCC)") (class "Default")
      (node (ref "L2") (pin "1") (pinfunction "1_1") (pintype "passive"))
      (node (ref "U2") (pin "10") (pinfunction "DCC_10") (pintype "bidirectional"))
    )
    (net (code "34") (name "Net-(U2-DEC4)") (class "Default")
      (node (ref "C7") (pin "1") (pinfunction "1_1") (pintype "passive"))
      (node (ref "L2") (pin "2") (pinfunction "2_2") (pintype "passive"))
      (node (ref "U2") (pin "9") (pinfunction "DEC4_9") (pintype "bidirectional"))
    )
    (net (code "35") (name "Net-(U2-P0.00{slash}XL1)") (class "Default")
      (node (ref "C8") (pin "2") (pinfunction "2_2") (pintype "passive"))
      (node (ref "U2") (pin "13") (pinfunction "P0.00/XL1_13") (pintype "bidirectional"))
      (node (ref "XTAL2") (pin "P$1") (pinfunction "1_P$1") (pintype "passive"))
    )
    (net (code "36") (name "Net-(U2-P0.01{slash}XL2)") (class "Default")
      (node (ref "C9") (pin "1") (pinfunction "1_1") (pintype "passive"))
      (node (ref "U2") (pin "14") (pinfunction "P0.01/XL2_14") (pintype "bidirectional"))
      (node (ref "XTAL2") (pin "P$2") (pinfunction "2_P$2") (pintype "passive"))
    )
    (net (code "37") (name "Net-(U3-BS1)") (class "Default")
      (node (ref "R6") (pin "2") (pinfunction "2_2") (pintype "passive"))
      (node (ref "U3") (pin "11") (pinfunction "BS1_11") (pintype "input"))
    )
    (net (code "38") (name "Net-(U3-C1N)") (class "Default")
      (node (ref "C15") (pin "1") (pinfunction "1_1") (pintype "passive"))
      (node (ref "U3") (pin "5") (pinfunction "C1N_5") (pintype "input"))
    )
    (net (code "39") (name "Net-(U3-C1P)") (class "Default")
      (node (ref "C15") (pin "2") (pinfunction "2_2") (pintype "passive"))
      (node (ref "U3") (pin "4") (pinfunction "C1P_4") (pintype "input"))
    )
    (net (code "40") (name "Net-(U3-C2N)") (class "Default")
      (node (ref "C13") (pin "1") (pinfunction "1_1") (pintype "passive"))
      (node (ref "U3") (pin "3") (pinfunction "C2N_3") (pintype "input"))
    )
    (net (code "41") (name "Net-(U3-C2P)") (class "Default")
      (node (ref "C13") (pin "2") (pinfunction "2_2") (pintype "passive"))
      (node (ref "U3") (pin "2") (pinfunction "C2P_2") (pintype "input"))
    )
    (net (code "42") (name "Net-(U3-IREF)") (class "Default")
      (node (ref "R7") (pin "1") (pinfunction "1_1") (pintype "passive"))
      (node (ref "U3") (pin "26") (pinfunction "IREF_26") (pintype "input"))
    )
    (net (code "43") (name "Net-(U3-VCC)") (class "Default")
      (node (ref "C16") (pin "2") (pinfunction "2_2") (pintype "passive"))
      (node (ref "U3") (pin "28") (pinfunction "VCC_28") (pintype "power_in"))
    )
    (net (code "44") (name "Net-(U3-VCOMH)") (class "Default")
      (node (ref "C18") (pin "2") (pinfunction "2_2") (pintype "passive"))
      (node (ref "U3") (pin "27") (pinfunction "VCOMH_27") (pintype "output"))
    )
    (net (code "45") (name "Net-(U4-OSCI)") (class "Default")
      (node (ref "U4") (pin "1") (pinfunction "OSCI_1") (pintype "bidirectional"))
      (node (ref "XTAL3") (pin "P$2") (pinfunction "2_P$2") (pintype "passive"))
    )
    (net (code "46") (name "Net-(U4-OSCO)") (class "Default")
      (node (ref "U4") (pin "2") (pinfunction "OSCO_2") (pintype "bidirectional"))
      (node (ref "XTAL3") (pin "P$1") (pinfunction "1_P$1") (pintype "passive"))
    )
    (net (code "47") (name "Net-(U5-USBDM)") (class "Default")
      (node (ref "R17") (pin "2") (pinfunction "2_2") (pintype "passive"))
      (node (ref "U5") (pin "12") (pinfunction "USBDM_12") (pintype "bidirectional"))
    )
    (net (code "48") (name "Net-(U5-USBDP)") (class "Default")
      (node (ref "R18") (pin "2") (pinfunction "2_2") (pintype "passive"))
      (node (ref "U5") (pin "11") (pinfunction "USBDP_11") (pintype "bidirectional"))
    )
    (net (code "49") (name "P0.09{slash}NFC1") (class "Default")
      (node (ref "C11") (pin "1") (pinfunction "1_1") (pintype "passive"))
      (node (ref "U2") (pin "22") (pinfunction "P0.09_22") (pintype "bidirectional"))
    )
    (net (code "50") (name "P0.10{slash}NFC2") (class "Default")
      (node (ref "C10") (pin "1") (pinfunction "1_1") (pintype "passive"))
      (node (ref "U2") (pin "23") (pinfunction "P0.10_23") (pintype "bidirectional"))
    )
    (net (code "51") (name "RESET") (class "Default")
      (node (ref "C14") (pin "2") (pinfunction "2_2") (pintype "passive"))
      (node (ref "CORTEX1") (pin "10") (pinfunction "~{RESET}_10") (pintype "bidirectional"))
      (node (ref "D1") (pin "+") (pinfunction "A_+") (pintype "passive"))
      (node (ref "R5") (pin "1") (pinfunction "1_1") (pintype "passive"))
      (node (ref "SW4") (pin "1") (pinfunction "A_1") (pintype "bidirectional"))
      (node (ref "U2") (pin "35") (pinfunction "P0.21/RESET_35") (pintype "bidirectional"))
    )
    (net (code "52") (name "RXD") (class "Default")
      (node (ref "U5") (pin "4") (pinfunction "RXD_4") (pintype "bidirectional"))
    )
    (net (code "53") (name "RXD.FT") (class "Default")
      (node (ref "R2") (pin "1") (pinfunction "1_1") (pintype "passive"))
    )
    (net (code "54") (name "RXD.NRF") (class "Default")
      (node (ref "R1") (pin "2") (pinfunction "2_2") (pintype "passive"))
      (node (ref "U2") (pin "21") (pinfunction "P0.08_21") (pintype "bidirectional"))
    )
    (net (code "55") (name "SCK") (class "Default")
      (node (ref "SD2") (pin "5") (pinfunction "SCLK_5") (pintype "input"))
      (node (ref "U2") (pin "26") (pinfunction "P0.12_26") (pintype "bidirectional"))
      (node (ref "U3") (pin "18") (pinfunction "D0/SPI_SCLK/I2C_SCK_18") (pintype "bidirectional"))
    )
    (net (code "56") (name "SCL") (class "Default")
      (node (ref "R9") (pin "1") (pinfunction "1_1") (pintype "passive"))
      (node (ref "U2") (pin "3") (pinfunction "P0.26_3") (pintype "bidirectional"))
      (node (ref "U4") (pin "6") (pinfunction "SCL_6") (pintype "bidirectional"))
    )
    (net (code "57") (name "SDA") (class "Default")
      (node (ref "R8") (pin "1") (pinfunction "1_1") (pintype "passive"))
      (node (ref "U2") (pin "2") (pinfunction "P0.25_2") (pintype "bidirectional"))
      (node (ref "U4") (pin "5") (pinfunction "SDA_5") (pintype "bidirectional"))
    )
    (net (code "58") (name "SWCLK") (class "Default")
      (node (ref "CORTEX1") (pin "4") (pinfunction "SWDCLK/TCK_4") (pintype "bidirectional"))
      (node (ref "U2") (pin "36") (pinfunction "SWDCLK_36") (pintype "bidirectional"))
    )
    (net (code "59") (name "SWDIO") (class "Default")
      (node (ref "CORTEX1") (pin "2") (pinfunction "SWDIO/TMS_2") (pintype "bidirectional"))
      (node (ref "U2") (pin "37") (pinfunction "SWDIO_37") (pintype "bidirectional"))
    )
    (net (code "60") (name "SWO") (class "Default")
      (node (ref "CORTEX1") (pin "6") (pinfunction "SWO/TDO_6") (pintype "bidirectional"))
      (node (ref "U2") (pin "32") (pinfunction "P0.18/SWO_32") (pintype "bidirectional"))
    )
    (net (code "61") (name "TXD") (class "Default")
      (node (ref "U5") (pin "20") (pinfunction "TXD_20") (pintype "bidirectional"))
    )
    (net (code "62") (name "TXD.FT") (class "Default")
      (node (ref "R1") (pin "1") (pinfunction "1_1") (pintype "passive"))
    )
    (net (code "63") (name "TXD.NRF") (class "Default")
      (node (ref "R2") (pin "2") (pinfunction "2_2") (pintype "passive"))
      (node (ref "U2") (pin "19") (pinfunction "P0.06_19") (pintype "bidirectional"))
    )
    (net (code "64") (name "USB+") (class "Default")
      (node (ref "C23") (pin "1") (pinfunction "1_1") (pintype "passive"))
      (node (ref "R18") (pin "1") (pinfunction "1_1") (pintype "passive"))
      (node (ref "USB2") (pin "3") (pinfunction "D+_3") (pintype "bidirectional"))
    )
    (net (code "65") (name "USB-") (class "Default")
      (node (ref "C24") (pin "2") (pinfunction "2_2") (pintype "passive"))
      (node (ref "R17") (pin "1") (pinfunction "1_1") (pintype "passive"))
      (node (ref "USB2") (pin "2") (pinfunction "D-_2") (pintype "bidirectional"))
    )
    (net (code "66") (name "VIN") (class "Default")
      (node (ref "C21") (pin "2") (pinfunction "2_2") (pintype "passive"))
      (node (ref "C5") (pin "2") (pinfunction "2_2") (pintype "passive"))
      (node (ref "CHRG2") (pin "4") (pinfunction "VIN_4") (pintype "power_in"))
      (node (ref "D4") (pin "-") (pinfunction "C_-") (pintype "passive"))
      (node (ref "D5") (pin "-") (pinfunction "C_-") (pintype "passive"))
      (node (ref "LDO2") (pin "1") (pinfunction "IN_1") (pintype "bidirectional"))
      (node (ref "LDO2") (pin "3") (pinfunction "EN_3") (pintype "bidirectional"))
      (node (ref "R12") (pin "2") (pinfunction "2_2") (pintype "passive"))
    )
    (net (code "67") (name "VLIPO") (class "Default")
      (node (ref "C20") (pin "1") (pinfunction "1_1") (pintype "passive"))
      (node (ref "CHRG2") (pin "3") (pinfunction "VBAT_3") (pintype "power_in"))
      (node (ref "D4") (pin "+") (pinfunction "A_+") (pintype "passive"))
      (node (ref "J2") (pin "2") (pinfunction "2_2") (pintype "passive"))
      (node (ref "R13") (pin "2") (pinfunction "2_2") (pintype "passive"))
    )
    (net (code "68") (name "VUSB") (class "Default")
      (node (ref "D5") (pin "+") (pinfunction "A_+") (pintype "passive"))
      (node (ref "U5") (pin "15") (pinfunction "VCC_15") (pintype "bidirectional"))
      (node (ref "USB2") (pin "1") (pinfunction "V+_1") (pintype "bidirectional"))
    )
    (net (code "69") (name "unconnected-(CORTEX1-NC{slash}TDI-Pad8)") (class "Default")
      (node (ref "CORTEX1") (pin "8") (pinfunction "NC/TDI_8") (pintype "bidirectional"))
    )
    (net (code "70") (name "unconnected-(SD2-DAT1-Pad8)") (class "Default")
      (node (ref "SD2") (pin "8") (pinfunction "DAT1_8") (pintype "bidirectional"))
    )
    (net (code "71") (name "unconnected-(SD2-DAT2-Pad1)") (class "Default")
      (node (ref "SD2") (pin "1") (pinfunction "DAT2_1") (pintype "bidirectional"))
    )
    (net (code "72") (name "unconnected-(SW1-2-PadA2)") (class "Default")
      (node (ref "SW1") (pin "A2") (pinfunction "2_A2") (pintype "passive"))
    )
    (net (code "73") (name "unconnected-(SW2-2-PadA2)") (class "Default")
      (node (ref "SW2") (pin "A2") (pinfunction "2_A2") (pintype "passive"))
    )
    (net (code "74") (name "unconnected-(U2-P0.02{slash}AIN0-Pad15)") (class "Default")
      (node (ref "U2") (pin "15") (pinfunction "P0.02/AIN0_15") (pintype "bidirectional"))
    )
    (net (code "75") (name "unconnected-(U2-P0.23-Pad41)") (class "Default")
      (node (ref "U2") (pin "41") (pinfunction "P0.23_41") (pintype "bidirectional"))
    )
    (net (code "76") (name "unconnected-(U2-P0.24-Pad40)") (class "Default")
      (node (ref "U2") (pin "40") (pinfunction "P0.24_40") (pintype "bidirectional"))
    )
    (net (code "77") (name "unconnected-(U3-D2{slash}I2C_SDA-Pad20)") (class "Default")
      (node (ref "U3") (pin "20") (pinfunction "D2/I2C_SDA_20") (pintype "bidirectional"))
    )
    (net (code "78") (name "unconnected-(U3-D3-Pad21)") (class "Default")
      (node (ref "U3") (pin "21") (pinfunction "D3_21") (pintype "bidirectional"))
    )
    (net (code "79") (name "unconnected-(U3-D4-Pad22)") (class "Default")
      (node (ref "U3") (pin "22") (pinfunction "D4_22") (pintype "bidirectional"))
    )
    (net (code "80") (name "unconnected-(U3-D5-Pad23)") (class "Default")
      (node (ref "U3") (pin "23") (pinfunction "D5_23") (pintype "bidirectional"))
    )
    (net (code "81") (name "unconnected-(U3-D6-Pad24)") (class "Default")
      (node (ref "U3") (pin "24") (pinfunction "D6_24") (pintype "bidirectional"))
    )
    (net (code "82") (name "unconnected-(U3-D7-Pad25)") (class "Default")
      (node (ref "U3") (pin "25") (pinfunction "D7_25") (pintype "bidirectional"))
    )
    (net (code "83") (name "unconnected-(U3-E{slash}RD-Pad17)") (class "Default")
      (node (ref "U3") (pin "17") (pinfunction "E/RD_17") (pintype "input"))
    )
    (net (code "84") (name "unconnected-(U3-NC-Pad7)") (class "Default")
      (node (ref "U3") (pin "7") (pinfunction "NC_7") (pintype "no_connect"))
    )
    (net (code "85") (name "unconnected-(U3-R{slash}W-Pad16)") (class "Default")
      (node (ref "U3") (pin "16") (pinfunction "R/W_16") (pintype "input"))
    )
    (net (code "86") (name "unconnected-(U4-INT{slash}CLKOUT-Pad7)") (class "Default")
      (node (ref "U4") (pin "7") (pinfunction "INT/CLKOUT_7") (pintype "bidirectional"))
    )
    (net (code "87") (name "unconnected-(U5-CBUS0-Pad18)") (class "Default")
      (node (ref "U5") (pin "18") (pinfunction "CBUS0_18") (pintype "bidirectional"))
    )
    (net (code "88") (name "unconnected-(U5-CBUS3-Pad19)") (class "Default")
      (node (ref "U5") (pin "19") (pinfunction "CBUS3_19") (pintype "bidirectional"))
    )
    (net (code "89") (name "unconnected-(U5-~{DCD}-Pad8)") (class "Default")
      (node (ref "U5") (pin "8") (pinfunction "~{DCD}_8") (pintype "bidirectional"))
    )
    (net (code "90") (name "unconnected-(U5-~{DSR}-Pad7)") (class "Default")
      (node (ref "U5") (pin "7") (pinfunction "~{DSR}_7") (pintype "bidirectional"))
    )
    (net (code "91") (name "unconnected-(U5-~{RI}-Pad5)") (class "Default")
      (node (ref "U5") (pin "5") (pinfunction "~{RI}_5") (pintype "bidirectional"))
    )
    (net (code "92") (name "unconnected-(U5-~{RTS}-Pad2)") (class "Default")
      (node (ref "U5") (pin "2") (pinfunction "~{RTS}_2") (pintype "bidirectional"))
    )
    (net (code "93") (name "unconnected-(USB2-ID-Pad4)") (class "Default")
      (node (ref "USB2") (pin "4") (pinfunction "ID_4") (pintype "bidirectional"))
    )
  )
)
